# AB_RADIO.net
KiCad netlist of a schematic drawn in EAGLE
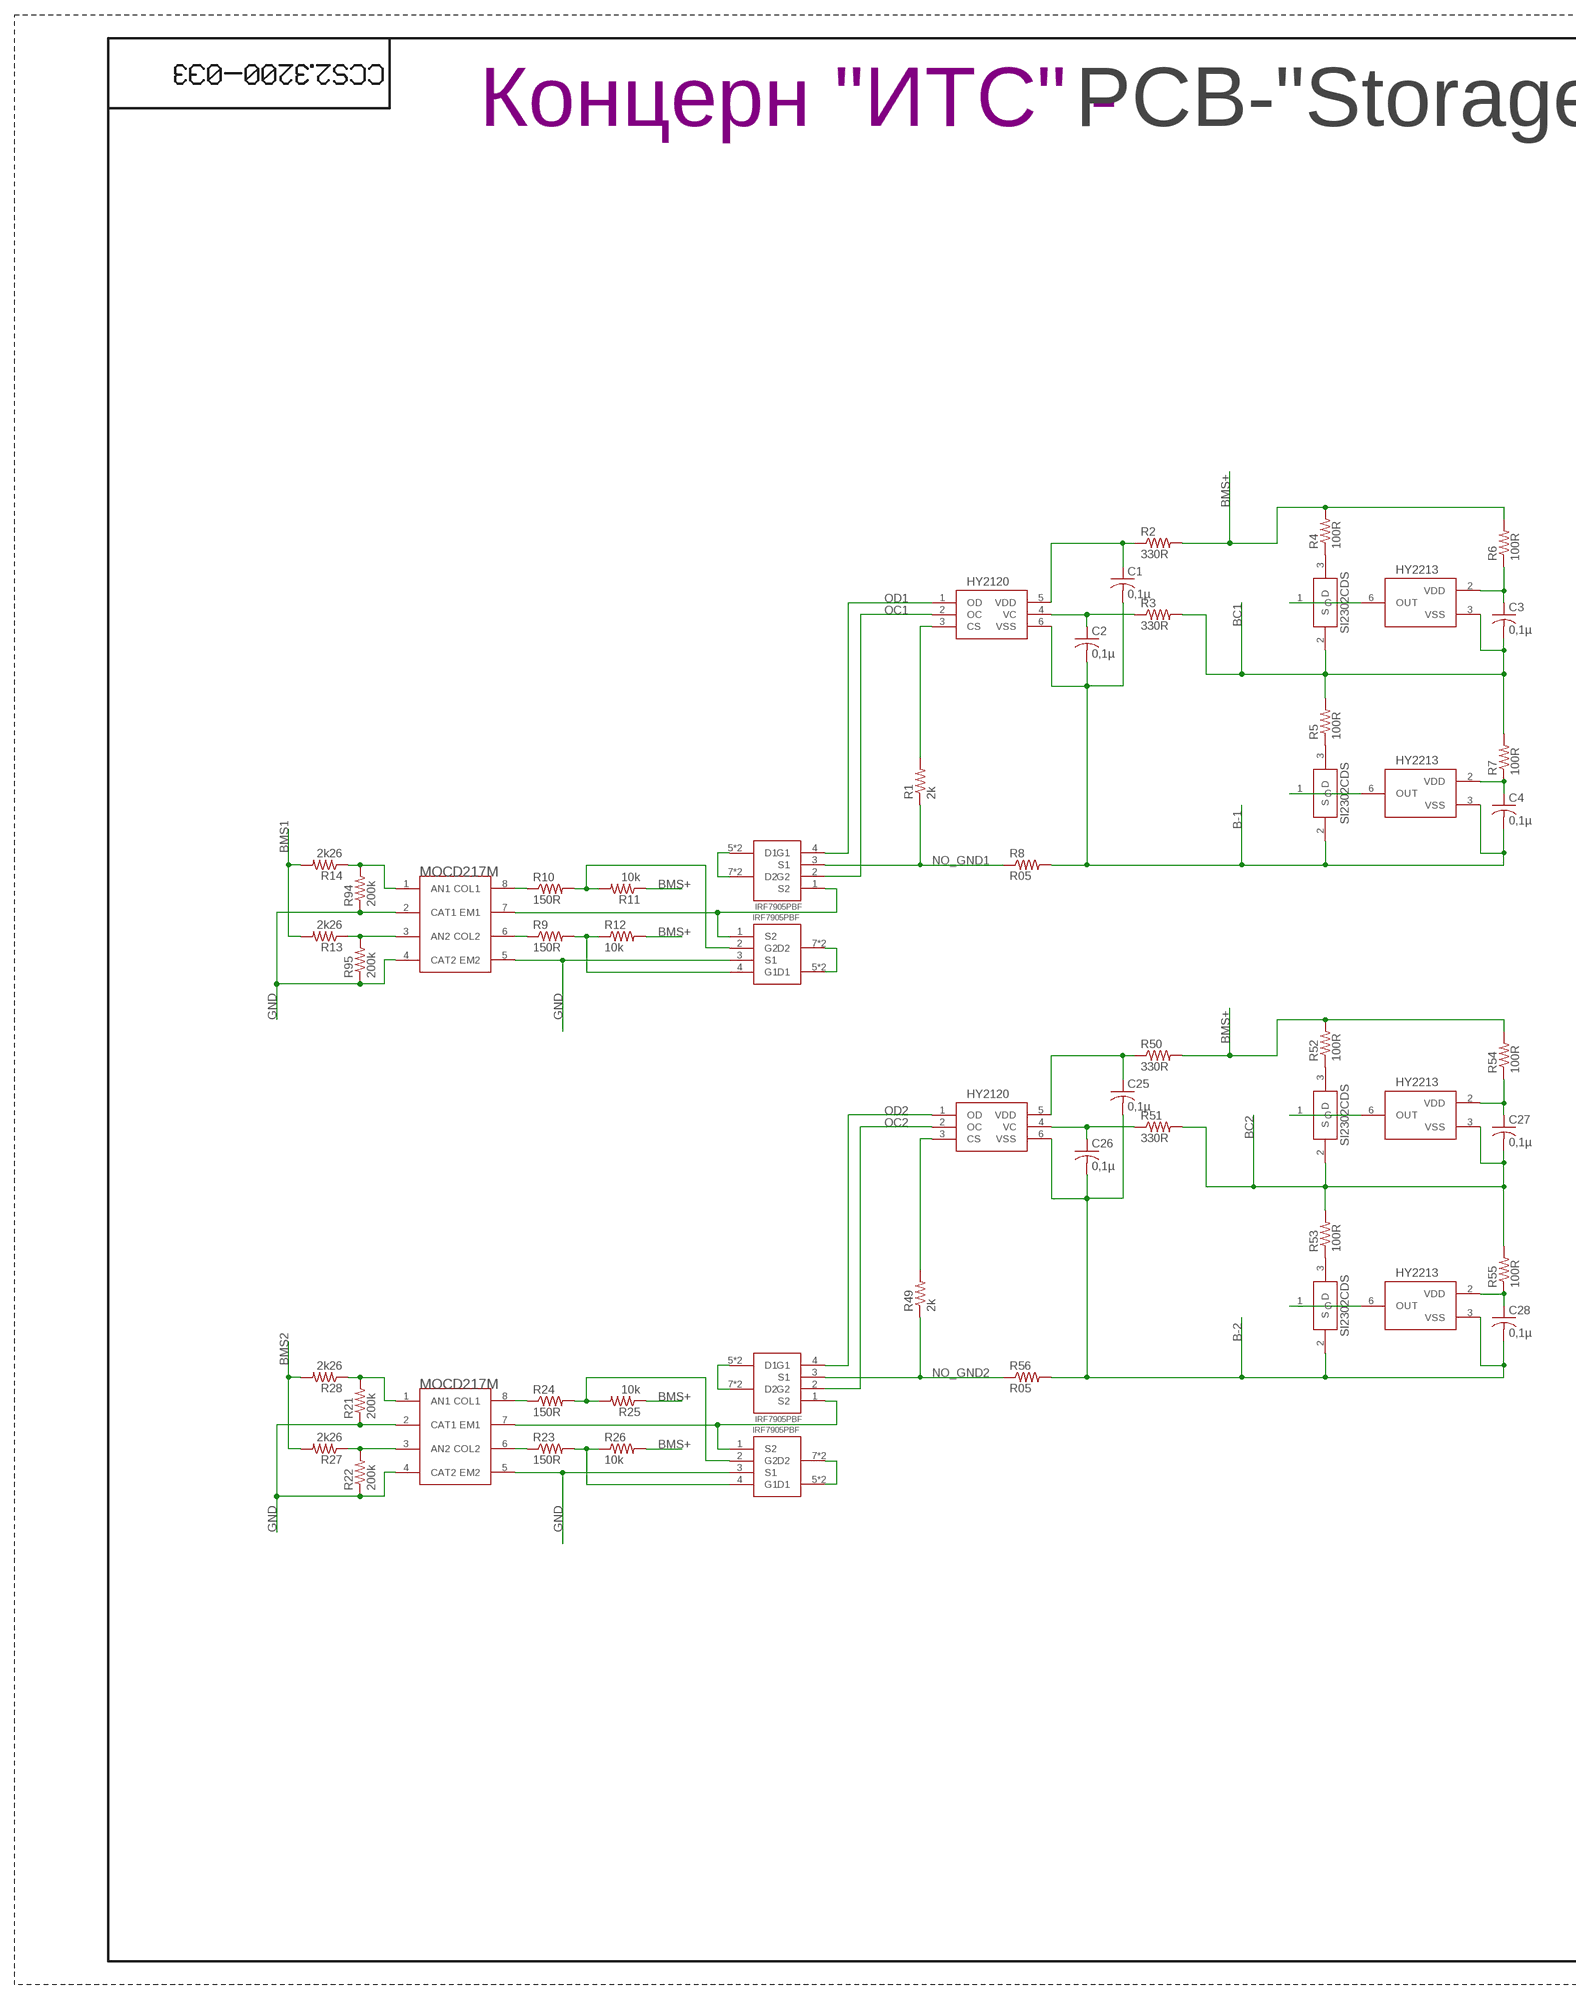
[diagram p0: schematic, sheet 1, part 1 of 2]
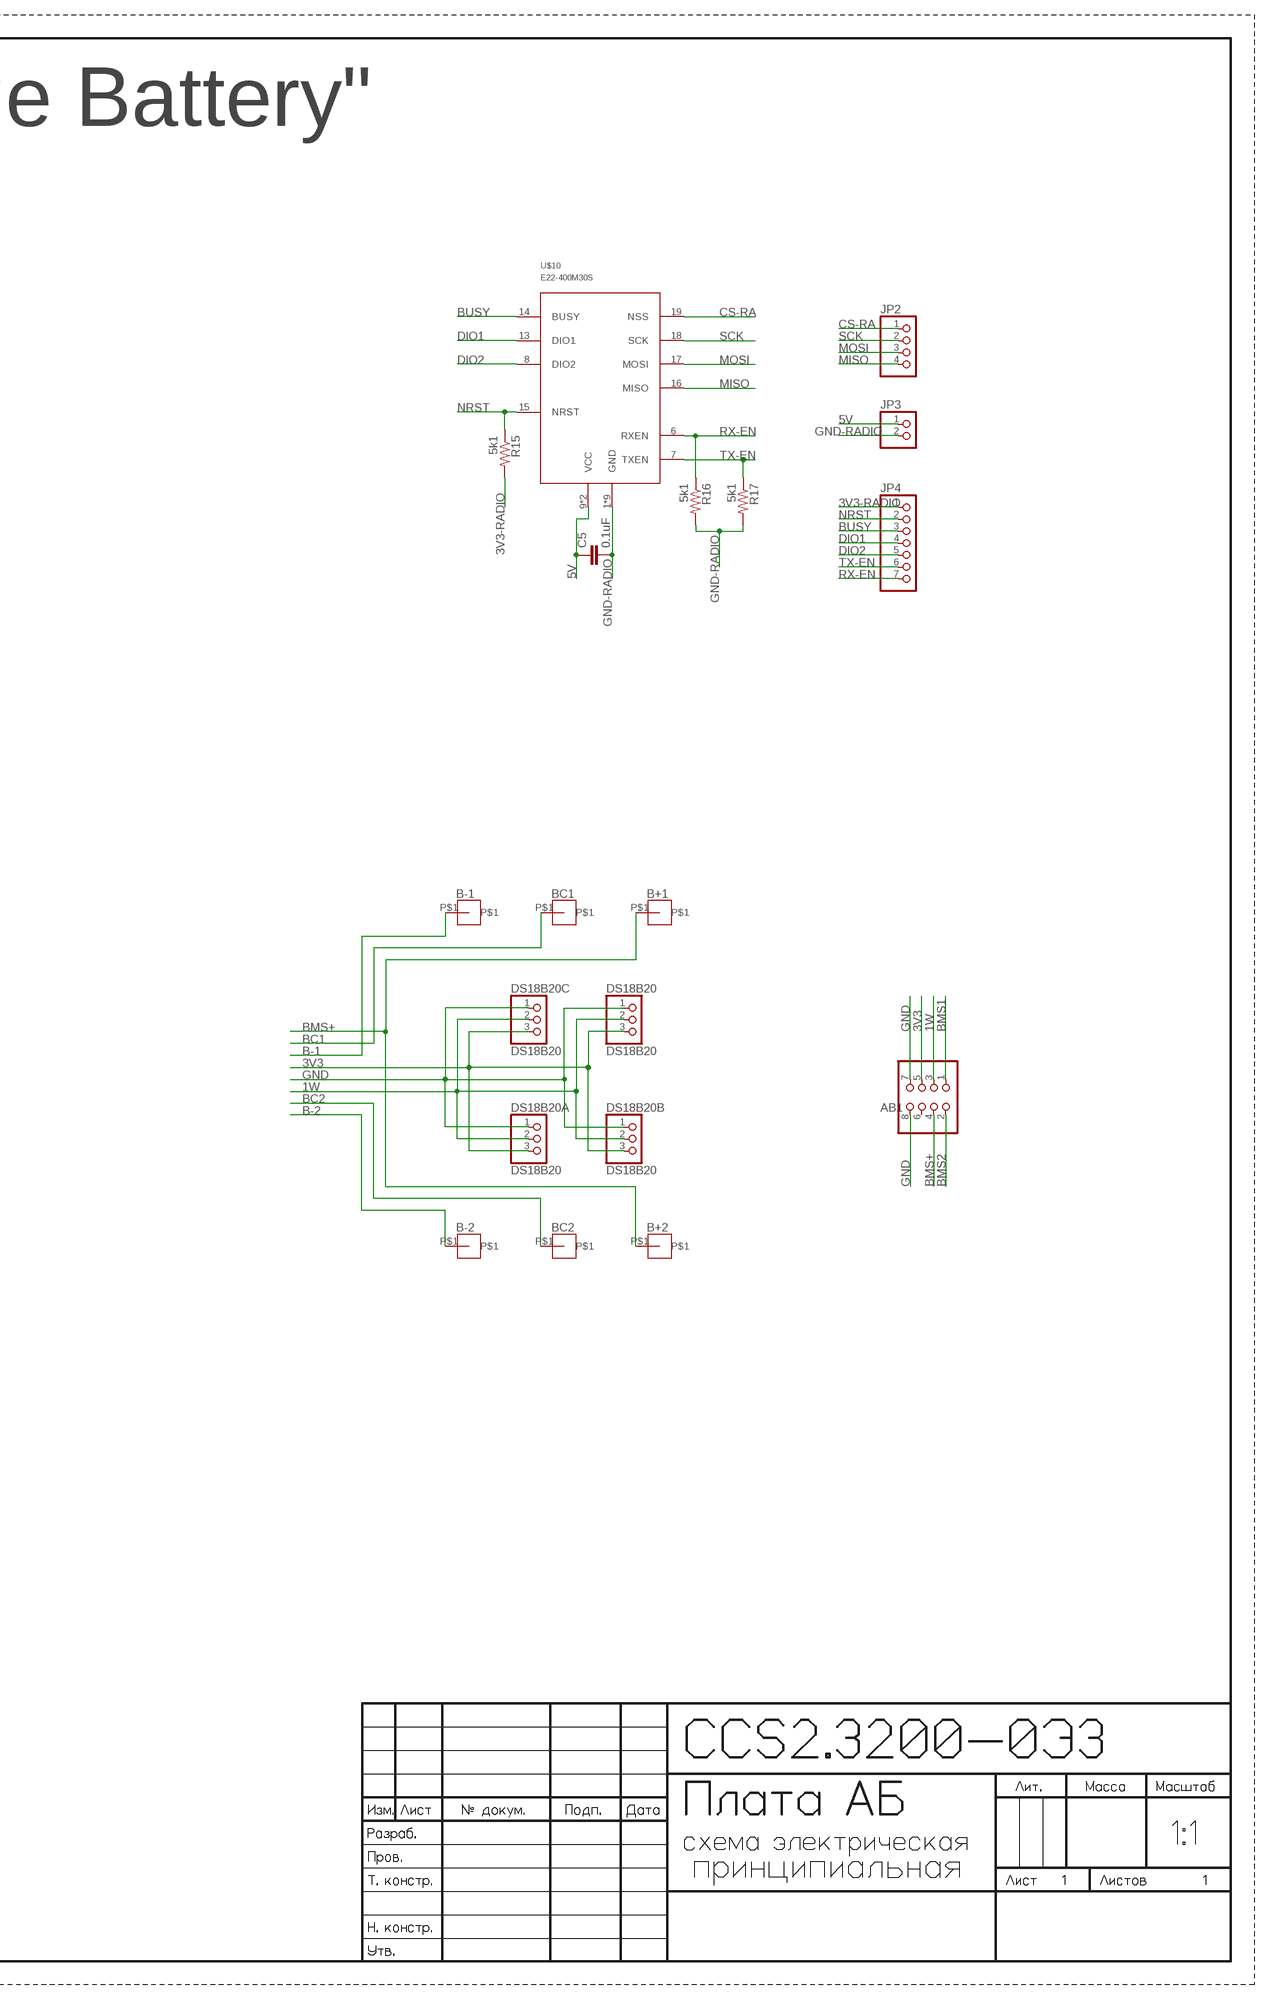
[diagram p1: schematic, sheet 1, part 2 of 2]

(export (version "E")
  (design (tool "Eeschema 10.0.6"))
  (components
    (comp (ref "AB1")
      (value "PINHD-2X4")
      (footprint "eagle-import:2X04")
      (libsource (lib "eagle-import") (part "PINHD-2X4"))
    )
    (comp (ref "B+1")
      (value "BATTERY")
      (footprint "eagle-import:BATTERY")
      (libsource (lib "eagle-import") (part "BATTERY"))
    )
    (comp (ref "B+2")
      (value "BATTERY")
      (footprint "eagle-import:BATTERY")
      (libsource (lib "eagle-import") (part "BATTERY"))
    )
    (comp (ref "B-1")
      (value "BATTERY")
      (footprint "eagle-import:BATTERY")
      (libsource (lib "eagle-import") (part "BATTERY"))
    )
    (comp (ref "B-2")
      (value "BATTERY")
      (footprint "eagle-import:BATTERY")
      (libsource (lib "eagle-import") (part "BATTERY"))
    )
    (comp (ref "BC1")
      (value "BATTERY")
      (footprint "eagle-import:BATTERY")
      (libsource (lib "eagle-import") (part "BATTERY"))
    )
    (comp (ref "BC2")
      (value "BATTERY")
      (footprint "eagle-import:BATTERY")
      (libsource (lib "eagle-import") (part "BATTERY"))
    )
    (comp (ref "C1")
      (value "0,1µ")
      (footprint "eagle-import:C0603")
      (libsource (lib "eagle-import") (part "C-USC0603"))
    )
    (comp (ref "C2")
      (value "0,1µ")
      (footprint "eagle-import:C0603")
      (libsource (lib "eagle-import") (part "C-USC0603"))
    )
    (comp (ref "C3")
      (value "0,1µ")
      (footprint "eagle-import:C0603")
      (libsource (lib "eagle-import") (part "C-USC0603"))
    )
    (comp (ref "C4")
      (value "0,1µ")
      (footprint "eagle-import:C0603")
      (libsource (lib "eagle-import") (part "C-USC0603"))
    )
    (comp (ref "C5")
      (value "0.1uF")
      (footprint "eagle-import:C0603")
      (libsource (lib "eagle-import") (part "C-EUC0603"))
    )
    (comp (ref "C25")
      (value "0,1µ")
      (footprint "eagle-import:C0603")
      (libsource (lib "eagle-import") (part "C-USC0603"))
    )
    (comp (ref "C26")
      (value "0,1µ")
      (footprint "eagle-import:C0603")
      (libsource (lib "eagle-import") (part "C-USC0603"))
    )
    (comp (ref "C27")
      (value "0,1µ")
      (footprint "eagle-import:C0603")
      (libsource (lib "eagle-import") (part "C-USC0603"))
    )
    (comp (ref "C28")
      (value "0,1µ")
      (footprint "eagle-import:C0603")
      (libsource (lib "eagle-import") (part "C-USC0603"))
    )
    (comp (ref "DS18B20")
      (value "DS18B20")
      (footprint "eagle-import:CONNECT1X3")
      (libsource (lib "eagle-import") (part "CONNECT1X3"))
    )
    (comp (ref "DS18B20A")
      (value "DS18B20")
      (footprint "eagle-import:CONNECT1X3")
      (libsource (lib "eagle-import") (part "CONNECT1X3"))
    )
    (comp (ref "DS18B20B")
      (value "DS18B20")
      (footprint "eagle-import:CONNECT1X3")
      (libsource (lib "eagle-import") (part "CONNECT1X3"))
    )
    (comp (ref "DS18B20C")
      (value "DS18B20")
      (footprint "eagle-import:CONNECT1X3")
      (libsource (lib "eagle-import") (part "CONNECT1X3"))
    )
    (comp (ref "JP2")
      (value "PINHD-1X4")
      (footprint "eagle-import:1X04")
      (libsource (lib "eagle-import") (part "PINHD-1X4"))
    )
    (comp (ref "JP3")
      (value "PINHD-1X2")
      (footprint "eagle-import:1X02")
      (libsource (lib "eagle-import") (part "PINHD-1X2"))
    )
    (comp (ref "JP4")
      (value "PINHD-1X7")
      (footprint "eagle-import:1X07")
      (libsource (lib "eagle-import") (part "PINHD-1X7"))
    )
    (comp (ref "R1")
      (value "2k")
      (footprint "eagle-import:R0603")
      (libsource (lib "eagle-import") (part "resistor_348_R-US_R0603"))
    )
    (comp (ref "R2")
      (value "330R")
      (footprint "eagle-import:R0603")
      (libsource (lib "eagle-import") (part "resistor_348_R-US_R0603"))
    )
    (comp (ref "R3")
      (value "330R")
      (footprint "eagle-import:R0603")
      (libsource (lib "eagle-import") (part "resistor_348_R-US_R0603"))
    )
    (comp (ref "R4")
      (value "100R")
      (footprint "eagle-import:R0603")
      (libsource (lib "eagle-import") (part "resistor_348_R-US_R0603"))
    )
    (comp (ref "R5")
      (value "100R")
      (footprint "eagle-import:R0603")
      (libsource (lib "eagle-import") (part "resistor_348_R-US_R0603"))
    )
    (comp (ref "R6")
      (value "100R")
      (footprint "eagle-import:R0603")
      (libsource (lib "eagle-import") (part "resistor_348_R-US_R0603"))
    )
    (comp (ref "R7")
      (value "100R")
      (footprint "eagle-import:R0603")
      (libsource (lib "eagle-import") (part "resistor_348_R-US_R0603"))
    )
    (comp (ref "R8")
      (value "R05")
      (footprint "eagle-import:R2512")
      (libsource (lib "eagle-import") (part "R-US_R2512"))
    )
    (comp (ref "R9")
      (value "150R")
      (footprint "eagle-import:R0603")
      (libsource (lib "eagle-import") (part "resistor_348_R-US_R0603"))
    )
    (comp (ref "R10")
      (value "150R")
      (footprint "eagle-import:R0603")
      (libsource (lib "eagle-import") (part "resistor_348_R-US_R0603"))
    )
    (comp (ref "R11")
      (value "10k")
      (footprint "eagle-import:R0603")
      (libsource (lib "eagle-import") (part "resistor_348_R-US_R0603"))
    )
    (comp (ref "R12")
      (value "10k")
      (footprint "eagle-import:R0603")
      (libsource (lib "eagle-import") (part "resistor_348_R-US_R0603"))
    )
    (comp (ref "R13")
      (value "2k26")
      (footprint "eagle-import:R0603")
      (libsource (lib "eagle-import") (part "resistor_348_R-US_R0603"))
    )
    (comp (ref "R14")
      (value "2k26")
      (footprint "eagle-import:R0603")
      (libsource (lib "eagle-import") (part "resistor_348_R-US_R0603"))
    )
    (comp (ref "R15")
      (value "5k1")
      (footprint "eagle-import:R0603")
      (libsource (lib "eagle-import") (part "resistor_348_R-US_R0603"))
    )
    (comp (ref "R16")
      (value "5k1")
      (footprint "eagle-import:R0603")
      (libsource (lib "eagle-import") (part "resistor_348_R-US_R0603"))
    )
    (comp (ref "R17")
      (value "5k1")
      (footprint "eagle-import:R0603")
      (libsource (lib "eagle-import") (part "resistor_348_R-US_R0603"))
    )
    (comp (ref "R21")
      (value "200k")
      (footprint "eagle-import:R0603")
      (libsource (lib "eagle-import") (part "resistor_348_R-US_R0603"))
    )
    (comp (ref "R22")
      (value "200k")
      (footprint "eagle-import:R0603")
      (libsource (lib "eagle-import") (part "resistor_348_R-US_R0603"))
    )
    (comp (ref "R23")
      (value "150R")
      (footprint "eagle-import:R0603")
      (libsource (lib "eagle-import") (part "resistor_348_R-US_R0603"))
    )
    (comp (ref "R24")
      (value "150R")
      (footprint "eagle-import:R0603")
      (libsource (lib "eagle-import") (part "resistor_348_R-US_R0603"))
    )
    (comp (ref "R25")
      (value "10k")
      (footprint "eagle-import:R0603")
      (libsource (lib "eagle-import") (part "resistor_348_R-US_R0603"))
    )
    (comp (ref "R26")
      (value "10k")
      (footprint "eagle-import:R0603")
      (libsource (lib "eagle-import") (part "resistor_348_R-US_R0603"))
    )
    (comp (ref "R27")
      (value "2k26")
      (footprint "eagle-import:R0603")
      (libsource (lib "eagle-import") (part "resistor_348_R-US_R0603"))
    )
    (comp (ref "R28")
      (value "2k26")
      (footprint "eagle-import:R0603")
      (libsource (lib "eagle-import") (part "resistor_348_R-US_R0603"))
    )
    (comp (ref "R49")
      (value "2k")
      (footprint "eagle-import:R0603")
      (libsource (lib "eagle-import") (part "resistor_348_R-US_R0603"))
    )
    (comp (ref "R50")
      (value "330R")
      (footprint "eagle-import:R0603")
      (libsource (lib "eagle-import") (part "resistor_348_R-US_R0603"))
    )
    (comp (ref "R51")
      (value "330R")
      (footprint "eagle-import:R0603")
      (libsource (lib "eagle-import") (part "resistor_348_R-US_R0603"))
    )
    (comp (ref "R52")
      (value "100R")
      (footprint "eagle-import:R0603")
      (libsource (lib "eagle-import") (part "resistor_348_R-US_R0603"))
    )
    (comp (ref "R53")
      (value "100R")
      (footprint "eagle-import:R0603")
      (libsource (lib "eagle-import") (part "resistor_348_R-US_R0603"))
    )
    (comp (ref "R54")
      (value "100R")
      (footprint "eagle-import:R0603")
      (libsource (lib "eagle-import") (part "resistor_348_R-US_R0603"))
    )
    (comp (ref "R55")
      (value "100R")
      (footprint "eagle-import:R0603")
      (libsource (lib "eagle-import") (part "resistor_348_R-US_R0603"))
    )
    (comp (ref "R56")
      (value "R05")
      (footprint "eagle-import:R2512")
      (libsource (lib "eagle-import") (part "R-US_R2512"))
    )
    (comp (ref "R94")
      (value "200k")
      (footprint "eagle-import:R0603")
      (libsource (lib "eagle-import") (part "resistor_348_R-US_R0603"))
    )
    (comp (ref "R95")
      (value "200k")
      (footprint "eagle-import:R0603")
      (libsource (lib "eagle-import") (part "resistor_348_R-US_R0603"))
    )
    (comp (ref "U$1")
      (value "PCB-\"Storage Battery\"")
      (footprint "eagle-import:ITS-LOGO")
      (libsource (lib "eagle-import") (part "ITS-LOGOPCB-{dblquote}{dblquote}"))
    )
    (comp (ref "U$2")
      (value "MOCD217M")
      (footprint "eagle-import:SOIC8")
      (libsource (lib "eagle-import") (part "MOCD217M"))
    )
    (comp (ref "U$3")
      (value "HY2120")
      (footprint "eagle-import:SOT23-6")
      (libsource (lib "eagle-import") (part "HY2120"))
    )
    (comp (ref "U$4")
      (value "HY2213\"")
      (footprint "eagle-import:SOT23-6")
      (libsource (lib "eagle-import") (part "HY2213{dblquote}"))
    )
    (comp (ref "U$5")
      (value "HY2213\"")
      (footprint "eagle-import:SOT23-6")
      (libsource (lib "eagle-import") (part "HY2213{dblquote}"))
    )
    (comp (ref "U$6")
      (value "SI2302CDS")
      (footprint "eagle-import:SOT23-3")
      (libsource (lib "eagle-import") (part "SI2302CDS"))
    )
    (comp (ref "U$7")
      (value "SI2302CDS")
      (footprint "eagle-import:SOT23-3")
      (libsource (lib "eagle-import") (part "SI2302CDS"))
    )
    (comp (ref "U$8")
      (value "IRF7905PBF")
      (footprint "eagle-import:SO8")
      (libsource (lib "eagle-import") (part "IRF7905PBF"))
    )
    (comp (ref "U$9")
      (value "IRF7905PBF")
      (footprint "eagle-import:SO8")
      (libsource (lib "eagle-import") (part "IRF7905PBF"))
    )
    (comp (ref "U$10")
      (value "E22-400M30S")
      (footprint "eagle-import:E22-400M30S")
      (libsource (lib "eagle-import") (part "E22-400M30S"))
    )
    (comp (ref "U$11")
      (value "MOCD217M")
      (footprint "eagle-import:SOIC8")
      (libsource (lib "eagle-import") (part "MOCD217M"))
    )
    (comp (ref "U$12")
      (value "IRF7905PBF")
      (footprint "eagle-import:SO8")
      (libsource (lib "eagle-import") (part "IRF7905PBF"))
    )
    (comp (ref "U$13")
      (value "IRF7905PBF")
      (footprint "eagle-import:SO8")
      (libsource (lib "eagle-import") (part "IRF7905PBF"))
    )
    (comp (ref "U$45")
      (value "HY2120")
      (footprint "eagle-import:SOT23-6")
      (libsource (lib "eagle-import") (part "HY2120"))
    )
    (comp (ref "U$46")
      (value "HY2213\"")
      (footprint "eagle-import:SOT23-6")
      (libsource (lib "eagle-import") (part "HY2213{dblquote}"))
    )
    (comp (ref "U$47")
      (value "HY2213\"")
      (footprint "eagle-import:SOT23-6")
      (libsource (lib "eagle-import") (part "HY2213{dblquote}"))
    )
    (comp (ref "U$48")
      (value "SI2302CDS")
      (footprint "eagle-import:SOT23-3")
      (libsource (lib "eagle-import") (part "SI2302CDS"))
    )
    (comp (ref "U$49")
      (value "SI2302CDS")
      (footprint "eagle-import:SOT23-3")
      (libsource (lib "eagle-import") (part "SI2302CDS"))
    )
  )
  (nets
    (net (code "1") (name "/1W") (class "Default")
      (node (ref "AB1") (pin "3") (pinfunction "3_3") (pintype "passive"))
      (node (ref "DS18B20") (pin "2") (pinfunction "2_2") (pintype "passive"))
      (node (ref "DS18B20A") (pin "2") (pinfunction "2_2") (pintype "passive"))
      (node (ref "DS18B20B") (pin "2") (pinfunction "2_2") (pintype "passive"))
      (node (ref "DS18B20C") (pin "2") (pinfunction "2_2") (pintype "passive"))
    )
    (net (code "2") (name "/3V3") (class "Default")
      (node (ref "AB1") (pin "5") (pinfunction "5_5") (pintype "passive"))
      (node (ref "DS18B20") (pin "3") (pinfunction "3_3") (pintype "passive"))
      (node (ref "DS18B20A") (pin "3") (pinfunction "3_3") (pintype "passive"))
      (node (ref "DS18B20B") (pin "3") (pinfunction "3_3") (pintype "passive"))
      (node (ref "DS18B20C") (pin "3") (pinfunction "3_3") (pintype "passive"))
    )
    (net (code "3") (name "/3V3-RADIO") (class "Default")
      (node (ref "JP4") (pin "1") (pinfunction "1_1") (pintype "passive"))
      (node (ref "R15") (pin "2") (pinfunction "2_2") (pintype "passive"))
    )
    (net (code "4") (name "/5V") (class "Default")
      (node (ref "C5") (pin "1") (pinfunction "1_1") (pintype "passive"))
      (node (ref "JP3") (pin "1") (pinfunction "1_1") (pintype "passive"))
      (node (ref "U$10") (pin "10") (pinfunction "VCC_10") (pintype "power_in"))
      (node (ref "U$10") (pin "9") (pinfunction "VCC_9") (pintype "power_in"))
    )
    (net (code "5") (name "/B-1") (class "Default")
      (node (ref "B-1") (pin "P$1") (pinfunction "P$1_P$1") (pintype "bidirectional"))
      (node (ref "C1") (pin "2") (pinfunction "2_2") (pintype "passive"))
      (node (ref "C2") (pin "2") (pinfunction "2_2") (pintype "passive"))
      (node (ref "C4") (pin "2") (pinfunction "2_2") (pintype "passive"))
      (node (ref "R8") (pin "2") (pinfunction "2_2") (pintype "passive"))
      (node (ref "U$3") (pin "6") (pinfunction "VSS_6") (pintype "bidirectional"))
      (node (ref "U$5") (pin "3") (pinfunction "VSS_3") (pintype "bidirectional"))
      (node (ref "U$7") (pin "2") (pinfunction "S_2") (pintype "bidirectional"))
    )
    (net (code "6") (name "/B-2") (class "Default")
      (node (ref "B-2") (pin "P$1") (pinfunction "P$1_P$1") (pintype "bidirectional"))
      (node (ref "C25") (pin "2") (pinfunction "2_2") (pintype "passive"))
      (node (ref "C26") (pin "2") (pinfunction "2_2") (pintype "passive"))
      (node (ref "C28") (pin "2") (pinfunction "2_2") (pintype "passive"))
      (node (ref "R56") (pin "2") (pinfunction "2_2") (pintype "passive"))
      (node (ref "U$45") (pin "6") (pinfunction "VSS_6") (pintype "bidirectional"))
      (node (ref "U$47") (pin "3") (pinfunction "VSS_3") (pintype "bidirectional"))
      (node (ref "U$49") (pin "2") (pinfunction "S_2") (pintype "bidirectional"))
    )
    (net (code "7") (name "/BC1") (class "Default")
      (node (ref "BC1") (pin "P$1") (pinfunction "P$1_P$1") (pintype "bidirectional"))
      (node (ref "C3") (pin "2") (pinfunction "2_2") (pintype "passive"))
      (node (ref "R3") (pin "2") (pinfunction "2_2") (pintype "passive"))
      (node (ref "R5") (pin "2") (pinfunction "2_2") (pintype "passive"))
      (node (ref "R7") (pin "2") (pinfunction "2_2") (pintype "passive"))
      (node (ref "U$4") (pin "3") (pinfunction "VSS_3") (pintype "bidirectional"))
      (node (ref "U$6") (pin "2") (pinfunction "S_2") (pintype "bidirectional"))
    )
    (net (code "8") (name "/BC2") (class "Default")
      (node (ref "BC2") (pin "P$1") (pinfunction "P$1_P$1") (pintype "bidirectional"))
      (node (ref "C27") (pin "2") (pinfunction "2_2") (pintype "passive"))
      (node (ref "R51") (pin "2") (pinfunction "2_2") (pintype "passive"))
      (node (ref "R53") (pin "2") (pinfunction "2_2") (pintype "passive"))
      (node (ref "R55") (pin "2") (pinfunction "2_2") (pintype "passive"))
      (node (ref "U$46") (pin "3") (pinfunction "VSS_3") (pintype "bidirectional"))
      (node (ref "U$48") (pin "2") (pinfunction "S_2") (pintype "bidirectional"))
    )
    (net (code "9") (name "/BMS+") (class "Default")
      (node (ref "AB1") (pin "4") (pinfunction "4_4") (pintype "passive"))
      (node (ref "B+1") (pin "P$1") (pinfunction "P$1_P$1") (pintype "bidirectional"))
      (node (ref "B+2") (pin "P$1") (pinfunction "P$1_P$1") (pintype "bidirectional"))
      (node (ref "R11") (pin "1") (pinfunction "1_1") (pintype "passive"))
      (node (ref "R12") (pin "2") (pinfunction "2_2") (pintype "passive"))
      (node (ref "R2") (pin "2") (pinfunction "2_2") (pintype "passive"))
      (node (ref "R25") (pin "1") (pinfunction "1_1") (pintype "passive"))
      (node (ref "R26") (pin "2") (pinfunction "2_2") (pintype "passive"))
      (node (ref "R4") (pin "2") (pinfunction "2_2") (pintype "passive"))
      (node (ref "R50") (pin "2") (pinfunction "2_2") (pintype "passive"))
      (node (ref "R52") (pin "2") (pinfunction "2_2") (pintype "passive"))
      (node (ref "R54") (pin "2") (pinfunction "2_2") (pintype "passive"))
      (node (ref "R6") (pin "2") (pinfunction "2_2") (pintype "passive"))
    )
    (net (code "10") (name "/BMS1") (class "Default")
      (node (ref "AB1") (pin "1") (pinfunction "1_1") (pintype "passive"))
      (node (ref "R13") (pin "2") (pinfunction "2_2") (pintype "passive"))
      (node (ref "R14") (pin "2") (pinfunction "2_2") (pintype "passive"))
    )
    (net (code "11") (name "/BMS2") (class "Default")
      (node (ref "AB1") (pin "2") (pinfunction "2_2") (pintype "passive"))
      (node (ref "R27") (pin "2") (pinfunction "2_2") (pintype "passive"))
      (node (ref "R28") (pin "2") (pinfunction "2_2") (pintype "passive"))
    )
    (net (code "12") (name "/BUSY") (class "Default")
      (node (ref "JP4") (pin "3") (pinfunction "3_3") (pintype "passive"))
      (node (ref "U$10") (pin "14") (pinfunction "BUSY_14") (pintype "output"))
    )
    (net (code "13") (name "/CS-RA") (class "Default")
      (node (ref "JP2") (pin "1") (pinfunction "1_1") (pintype "passive"))
      (node (ref "U$10") (pin "19") (pinfunction "NSS_19") (pintype "input"))
    )
    (net (code "14") (name "/DIO1") (class "Default")
      (node (ref "JP4") (pin "4") (pinfunction "4_4") (pintype "passive"))
      (node (ref "U$10") (pin "13") (pinfunction "DIO1_13") (pintype "bidirectional"))
    )
    (net (code "15") (name "/DIO2") (class "Default")
      (node (ref "JP4") (pin "5") (pinfunction "5_5") (pintype "passive"))
      (node (ref "U$10") (pin "8") (pinfunction "DIO2_8") (pintype "bidirectional"))
    )
    (net (code "16") (name "/GND") (class "Default")
      (node (ref "AB1") (pin "7") (pinfunction "7_7") (pintype "passive"))
      (node (ref "AB1") (pin "8") (pinfunction "8_8") (pintype "passive"))
      (node (ref "DS18B20") (pin "1") (pinfunction "1_1") (pintype "passive"))
      (node (ref "DS18B20A") (pin "1") (pinfunction "1_1") (pintype "passive"))
      (node (ref "DS18B20B") (pin "1") (pinfunction "1_1") (pintype "passive"))
      (node (ref "DS18B20C") (pin "1") (pinfunction "1_1") (pintype "passive"))
      (node (ref "R21") (pin "1") (pinfunction "1_1") (pintype "passive"))
      (node (ref "R22") (pin "1") (pinfunction "1_1") (pintype "passive"))
      (node (ref "R94") (pin "1") (pinfunction "1_1") (pintype "passive"))
      (node (ref "R95") (pin "1") (pinfunction "1_1") (pintype "passive"))
      (node (ref "U$11") (pin "2") (pinfunction "CAT1_2") (pintype "bidirectional"))
      (node (ref "U$11") (pin "4") (pinfunction "CAT2_4") (pintype "bidirectional"))
      (node (ref "U$11") (pin "5") (pinfunction "EM2_5") (pintype "bidirectional"))
      (node (ref "U$12") (pin "3") (pinfunction "S1_3") (pintype "bidirectional"))
      (node (ref "U$2") (pin "2") (pinfunction "CAT1_2") (pintype "bidirectional"))
      (node (ref "U$2") (pin "4") (pinfunction "CAT2_4") (pintype "bidirectional"))
      (node (ref "U$2") (pin "5") (pinfunction "EM2_5") (pintype "bidirectional"))
      (node (ref "U$8") (pin "3") (pinfunction "S1_3") (pintype "bidirectional"))
    )
    (net (code "17") (name "/GND-RADIO") (class "Default")
      (node (ref "C5") (pin "2") (pinfunction "2_2") (pintype "passive"))
      (node (ref "JP3") (pin "2") (pinfunction "2_2") (pintype "passive"))
      (node (ref "R16") (pin "2") (pinfunction "2_2") (pintype "passive"))
      (node (ref "R17") (pin "2") (pinfunction "2_2") (pintype "passive"))
      (node (ref "U$10") (pin "1") (pinfunction "GND_1") (pintype "power_in"))
      (node (ref "U$10") (pin "11") (pinfunction "GND_11") (pintype "power_in"))
      (node (ref "U$10") (pin "12") (pinfunction "GND_12") (pintype "power_in"))
      (node (ref "U$10") (pin "2") (pinfunction "GND_2") (pintype "power_in"))
      (node (ref "U$10") (pin "20") (pinfunction "GND_20") (pintype "power_in"))
      (node (ref "U$10") (pin "22") (pinfunction "GND_22") (pintype "power_in"))
      (node (ref "U$10") (pin "3") (pinfunction "GND_3") (pintype "power_in"))
      (node (ref "U$10") (pin "4") (pinfunction "GND_4") (pintype "power_in"))
      (node (ref "U$10") (pin "5") (pinfunction "GND_5") (pintype "power_in"))
    )
    (net (code "18") (name "/MISO") (class "Default")
      (node (ref "JP2") (pin "4") (pinfunction "4_4") (pintype "passive"))
      (node (ref "U$10") (pin "16") (pinfunction "MISO_16") (pintype "output"))
    )
    (net (code "19") (name "/MOSI") (class "Default")
      (node (ref "JP2") (pin "3") (pinfunction "3_3") (pintype "passive"))
      (node (ref "U$10") (pin "17") (pinfunction "MOSI_17") (pintype "input"))
    )
    (net (code "20") (name "/NO_GND1") (class "Default")
      (node (ref "R1") (pin "1") (pinfunction "1_1") (pintype "passive"))
      (node (ref "R8") (pin "1") (pinfunction "1_1") (pintype "passive"))
      (node (ref "U$9") (pin "3") (pinfunction "S1_3") (pintype "bidirectional"))
    )
    (net (code "21") (name "/NO_GND2") (class "Default")
      (node (ref "R49") (pin "1") (pinfunction "1_1") (pintype "passive"))
      (node (ref "R56") (pin "1") (pinfunction "1_1") (pintype "passive"))
      (node (ref "U$13") (pin "3") (pinfunction "S1_3") (pintype "bidirectional"))
    )
    (net (code "22") (name "/NRST") (class "Default")
      (node (ref "JP4") (pin "2") (pinfunction "2_2") (pintype "passive"))
      (node (ref "R15") (pin "1") (pinfunction "1_1") (pintype "passive"))
      (node (ref "U$10") (pin "15") (pinfunction "NRST_15") (pintype "input"))
    )
    (net (code "23") (name "/OC1") (class "Default")
      (node (ref "U$3") (pin "2") (pinfunction "OC_2") (pintype "bidirectional"))
      (node (ref "U$9") (pin "2") (pinfunction "G2_2") (pintype "bidirectional"))
    )
    (net (code "24") (name "/OC2") (class "Default")
      (node (ref "U$13") (pin "2") (pinfunction "G2_2") (pintype "bidirectional"))
      (node (ref "U$45") (pin "2") (pinfunction "OC_2") (pintype "bidirectional"))
    )
    (net (code "25") (name "/OD1") (class "Default")
      (node (ref "U$3") (pin "1") (pinfunction "OD_1") (pintype "bidirectional"))
      (node (ref "U$9") (pin "4") (pinfunction "G1_4") (pintype "bidirectional"))
    )
    (net (code "26") (name "/OD2") (class "Default")
      (node (ref "U$13") (pin "4") (pinfunction "G1_4") (pintype "bidirectional"))
      (node (ref "U$45") (pin "1") (pinfunction "OD_1") (pintype "bidirectional"))
    )
    (net (code "27") (name "/RX-EN") (class "Default")
      (node (ref "JP4") (pin "7") (pinfunction "7_7") (pintype "passive"))
      (node (ref "R16") (pin "1") (pinfunction "1_1") (pintype "passive"))
      (node (ref "U$10") (pin "6") (pinfunction "RXEN_6") (pintype "input"))
    )
    (net (code "28") (name "/SCK") (class "Default")
      (node (ref "JP2") (pin "2") (pinfunction "2_2") (pintype "passive"))
      (node (ref "U$10") (pin "18") (pinfunction "SCK_18") (pintype "input"))
    )
    (net (code "29") (name "/TX-EN") (class "Default")
      (node (ref "JP4") (pin "6") (pinfunction "6_6") (pintype "passive"))
      (node (ref "R17") (pin "1") (pinfunction "1_1") (pintype "passive"))
      (node (ref "U$10") (pin "7") (pinfunction "TXEN_7") (pintype "input"))
    )
    (net (code "30") (name "Net-(U$2-AN1)") (class "Default")
      (node (ref "R14") (pin "1") (pinfunction "1_1") (pintype "passive"))
      (node (ref "R94") (pin "2") (pinfunction "2_2") (pintype "passive"))
      (node (ref "U$2") (pin "1") (pinfunction "AN1_1") (pintype "bidirectional"))
    )
    (net (code "31") (name "Net-(U$2-AN2)") (class "Default")
      (node (ref "R13") (pin "1") (pinfunction "1_1") (pintype "passive"))
      (node (ref "R95") (pin "2") (pinfunction "2_2") (pintype "passive"))
      (node (ref "U$2") (pin "3") (pinfunction "AN2_3") (pintype "bidirectional"))
    )
    (net (code "32") (name "Net-(U$2-COL1)") (class "Default")
      (node (ref "R10") (pin "1") (pinfunction "1_1") (pintype "passive"))
      (node (ref "U$2") (pin "8") (pinfunction "COL1_8") (pintype "bidirectional"))
    )
    (net (code "33") (name "Net-(U$2-COL2)") (class "Default")
      (node (ref "R9") (pin "1") (pinfunction "1_1") (pintype "passive"))
      (node (ref "U$2") (pin "6") (pinfunction "COL2_6") (pintype "bidirectional"))
    )
    (net (code "34") (name "Net-(U$2-EM1)") (class "Default")
      (node (ref "U$2") (pin "7") (pinfunction "EM1_7") (pintype "bidirectional"))
      (node (ref "U$8") (pin "1") (pinfunction "S2_1") (pintype "bidirectional"))
      (node (ref "U$9") (pin "1") (pinfunction "S2_1") (pintype "bidirectional"))
    )
    (net (code "35") (name "Net-(U$3-CS)") (class "Default")
      (node (ref "R1") (pin "2") (pinfunction "2_2") (pintype "passive"))
      (node (ref "U$3") (pin "3") (pinfunction "CS_3") (pintype "bidirectional"))
    )
    (net (code "36") (name "Net-(U$3-VC)") (class "Default")
      (node (ref "C2") (pin "1") (pinfunction "1_1") (pintype "passive"))
      (node (ref "R3") (pin "1") (pinfunction "1_1") (pintype "passive"))
      (node (ref "U$3") (pin "4") (pinfunction "VC_4") (pintype "bidirectional"))
    )
    (net (code "37") (name "Net-(U$3-VDD)") (class "Default")
      (node (ref "C1") (pin "1") (pinfunction "1_1") (pintype "passive"))
      (node (ref "R2") (pin "1") (pinfunction "1_1") (pintype "passive"))
      (node (ref "U$3") (pin "5") (pinfunction "VDD_5") (pintype "bidirectional"))
    )
    (net (code "38") (name "Net-(U$4-OUT)") (class "Default")
      (node (ref "U$4") (pin "6") (pinfunction "OUT_6") (pintype "bidirectional"))
      (node (ref "U$6") (pin "1") (pinfunction "G_1") (pintype "bidirectional"))
    )
    (net (code "39") (name "Net-(U$4-VDD)") (class "Default")
      (node (ref "C3") (pin "1") (pinfunction "1_1") (pintype "passive"))
      (node (ref "R6") (pin "1") (pinfunction "1_1") (pintype "passive"))
      (node (ref "U$4") (pin "2") (pinfunction "VDD_2") (pintype "bidirectional"))
    )
    (net (code "40") (name "Net-(U$5-OUT)") (class "Default")
      (node (ref "U$5") (pin "6") (pinfunction "OUT_6") (pintype "bidirectional"))
      (node (ref "U$7") (pin "1") (pinfunction "G_1") (pintype "bidirectional"))
    )
    (net (code "41") (name "Net-(U$5-VDD)") (class "Default")
      (node (ref "C4") (pin "1") (pinfunction "1_1") (pintype "passive"))
      (node (ref "R7") (pin "1") (pinfunction "1_1") (pintype "passive"))
      (node (ref "U$5") (pin "2") (pinfunction "VDD_2") (pintype "bidirectional"))
    )
    (net (code "42") (name "Net-(U$6-D)") (class "Default")
      (node (ref "R4") (pin "1") (pinfunction "1_1") (pintype "passive"))
      (node (ref "U$6") (pin "3") (pinfunction "D_3") (pintype "bidirectional"))
    )
    (net (code "43") (name "Net-(U$7-D)") (class "Default")
      (node (ref "R5") (pin "1") (pinfunction "1_1") (pintype "passive"))
      (node (ref "U$7") (pin "3") (pinfunction "D_3") (pintype "bidirectional"))
    )
    (net (code "44") (name "Net-(U$8-D1-Pad5)") (class "Default")
      (node (ref "U$8") (pin "5") (pinfunction "D1_5") (pintype "bidirectional"))
      (node (ref "U$8") (pin "6") (pinfunction "D1_6") (pintype "bidirectional"))
      (node (ref "U$8") (pin "7") (pinfunction "D2_7") (pintype "bidirectional"))
      (node (ref "U$8") (pin "8") (pinfunction "D2_8") (pintype "bidirectional"))
    )
    (net (code "45") (name "Net-(U$8-G1)") (class "Default")
      (node (ref "R12") (pin "1") (pinfunction "1_1") (pintype "passive"))
      (node (ref "R9") (pin "2") (pinfunction "2_2") (pintype "passive"))
      (node (ref "U$8") (pin "4") (pinfunction "G1_4") (pintype "bidirectional"))
    )
    (net (code "46") (name "Net-(U$8-G2)") (class "Default")
      (node (ref "R10") (pin "2") (pinfunction "2_2") (pintype "passive"))
      (node (ref "R11") (pin "2") (pinfunction "2_2") (pintype "passive"))
      (node (ref "U$8") (pin "2") (pinfunction "G2_2") (pintype "bidirectional"))
    )
    (net (code "47") (name "Net-(U$9-D1-Pad5)") (class "Default")
      (node (ref "U$9") (pin "5") (pinfunction "D1_5") (pintype "bidirectional"))
      (node (ref "U$9") (pin "6") (pinfunction "D1_6") (pintype "bidirectional"))
      (node (ref "U$9") (pin "7") (pinfunction "D2_7") (pintype "bidirectional"))
      (node (ref "U$9") (pin "8") (pinfunction "D2_8") (pintype "bidirectional"))
    )
    (net (code "48") (name "Net-(U$11-AN1)") (class "Default")
      (node (ref "R21") (pin "2") (pinfunction "2_2") (pintype "passive"))
      (node (ref "R28") (pin "1") (pinfunction "1_1") (pintype "passive"))
      (node (ref "U$11") (pin "1") (pinfunction "AN1_1") (pintype "bidirectional"))
    )
    (net (code "49") (name "Net-(U$11-AN2)") (class "Default")
      (node (ref "R22") (pin "2") (pinfunction "2_2") (pintype "passive"))
      (node (ref "R27") (pin "1") (pinfunction "1_1") (pintype "passive"))
      (node (ref "U$11") (pin "3") (pinfunction "AN2_3") (pintype "bidirectional"))
    )
    (net (code "50") (name "Net-(U$11-COL1)") (class "Default")
      (node (ref "R24") (pin "1") (pinfunction "1_1") (pintype "passive"))
      (node (ref "U$11") (pin "8") (pinfunction "COL1_8") (pintype "bidirectional"))
    )
    (net (code "51") (name "Net-(U$11-COL2)") (class "Default")
      (node (ref "R23") (pin "1") (pinfunction "1_1") (pintype "passive"))
      (node (ref "U$11") (pin "6") (pinfunction "COL2_6") (pintype "bidirectional"))
    )
    (net (code "52") (name "Net-(U$11-EM1)") (class "Default")
      (node (ref "U$11") (pin "7") (pinfunction "EM1_7") (pintype "bidirectional"))
      (node (ref "U$12") (pin "1") (pinfunction "S2_1") (pintype "bidirectional"))
      (node (ref "U$13") (pin "1") (pinfunction "S2_1") (pintype "bidirectional"))
    )
    (net (code "53") (name "Net-(U$12-D1-Pad5)") (class "Default")
      (node (ref "U$12") (pin "5") (pinfunction "D1_5") (pintype "bidirectional"))
      (node (ref "U$12") (pin "6") (pinfunction "D1_6") (pintype "bidirectional"))
      (node (ref "U$12") (pin "7") (pinfunction "D2_7") (pintype "bidirectional"))
      (node (ref "U$12") (pin "8") (pinfunction "D2_8") (pintype "bidirectional"))
    )
    (net (code "54") (name "Net-(U$12-G1)") (class "Default")
      (node (ref "R23") (pin "2") (pinfunction "2_2") (pintype "passive"))
      (node (ref "R26") (pin "1") (pinfunction "1_1") (pintype "passive"))
      (node (ref "U$12") (pin "4") (pinfunction "G1_4") (pintype "bidirectional"))
    )
    (net (code "55") (name "Net-(U$12-G2)") (class "Default")
      (node (ref "R24") (pin "2") (pinfunction "2_2") (pintype "passive"))
      (node (ref "R25") (pin "2") (pinfunction "2_2") (pintype "passive"))
      (node (ref "U$12") (pin "2") (pinfunction "G2_2") (pintype "bidirectional"))
    )
    (net (code "56") (name "Net-(U$13-D1-Pad5)") (class "Default")
      (node (ref "U$13") (pin "5") (pinfunction "D1_5") (pintype "bidirectional"))
      (node (ref "U$13") (pin "6") (pinfunction "D1_6") (pintype "bidirectional"))
      (node (ref "U$13") (pin "7") (pinfunction "D2_7") (pintype "bidirectional"))
      (node (ref "U$13") (pin "8") (pinfunction "D2_8") (pintype "bidirectional"))
    )
    (net (code "57") (name "Net-(U$45-CS)") (class "Default")
      (node (ref "R49") (pin "2") (pinfunction "2_2") (pintype "passive"))
      (node (ref "U$45") (pin "3") (pinfunction "CS_3") (pintype "bidirectional"))
    )
    (net (code "58") (name "Net-(U$45-VC)") (class "Default")
      (node (ref "C26") (pin "1") (pinfunction "1_1") (pintype "passive"))
      (node (ref "R51") (pin "1") (pinfunction "1_1") (pintype "passive"))
      (node (ref "U$45") (pin "4") (pinfunction "VC_4") (pintype "bidirectional"))
    )
    (net (code "59") (name "Net-(U$45-VDD)") (class "Default")
      (node (ref "C25") (pin "1") (pinfunction "1_1") (pintype "passive"))
      (node (ref "R50") (pin "1") (pinfunction "1_1") (pintype "passive"))
      (node (ref "U$45") (pin "5") (pinfunction "VDD_5") (pintype "bidirectional"))
    )
    (net (code "60") (name "Net-(U$46-OUT)") (class "Default")
      (node (ref "U$46") (pin "6") (pinfunction "OUT_6") (pintype "bidirectional"))
      (node (ref "U$48") (pin "1") (pinfunction "G_1") (pintype "bidirectional"))
    )
    (net (code "61") (name "Net-(U$46-VDD)") (class "Default")
      (node (ref "C27") (pin "1") (pinfunction "1_1") (pintype "passive"))
      (node (ref "R54") (pin "1") (pinfunction "1_1") (pintype "passive"))
      (node (ref "U$46") (pin "2") (pinfunction "VDD_2") (pintype "bidirectional"))
    )
    (net (code "62") (name "Net-(U$47-OUT)") (class "Default")
      (node (ref "U$47") (pin "6") (pinfunction "OUT_6") (pintype "bidirectional"))
      (node (ref "U$49") (pin "1") (pinfunction "G_1") (pintype "bidirectional"))
    )
    (net (code "63") (name "Net-(U$47-VDD)") (class "Default")
      (node (ref "C28") (pin "1") (pinfunction "1_1") (pintype "passive"))
      (node (ref "R55") (pin "1") (pinfunction "1_1") (pintype "passive"))
      (node (ref "U$47") (pin "2") (pinfunction "VDD_2") (pintype "bidirectional"))
    )
    (net (code "64") (name "Net-(U$48-D)") (class "Default")
      (node (ref "R52") (pin "1") (pinfunction "1_1") (pintype "passive"))
      (node (ref "U$48") (pin "3") (pinfunction "D_3") (pintype "bidirectional"))
    )
    (net (code "65") (name "Net-(U$49-D)") (class "Default")
      (node (ref "R53") (pin "1") (pinfunction "1_1") (pintype "passive"))
      (node (ref "U$49") (pin "3") (pinfunction "D_3") (pintype "bidirectional"))
    )
    (net (code "66") (name "unconnected-(AB1-Pad6)") (class "Default")
      (node (ref "AB1") (pin "6") (pinfunction "6_6") (pintype "passive"))
    )
  )
)
